# 180V_PSU.net
KiCad netlist of a schematic drawn in EAGLE
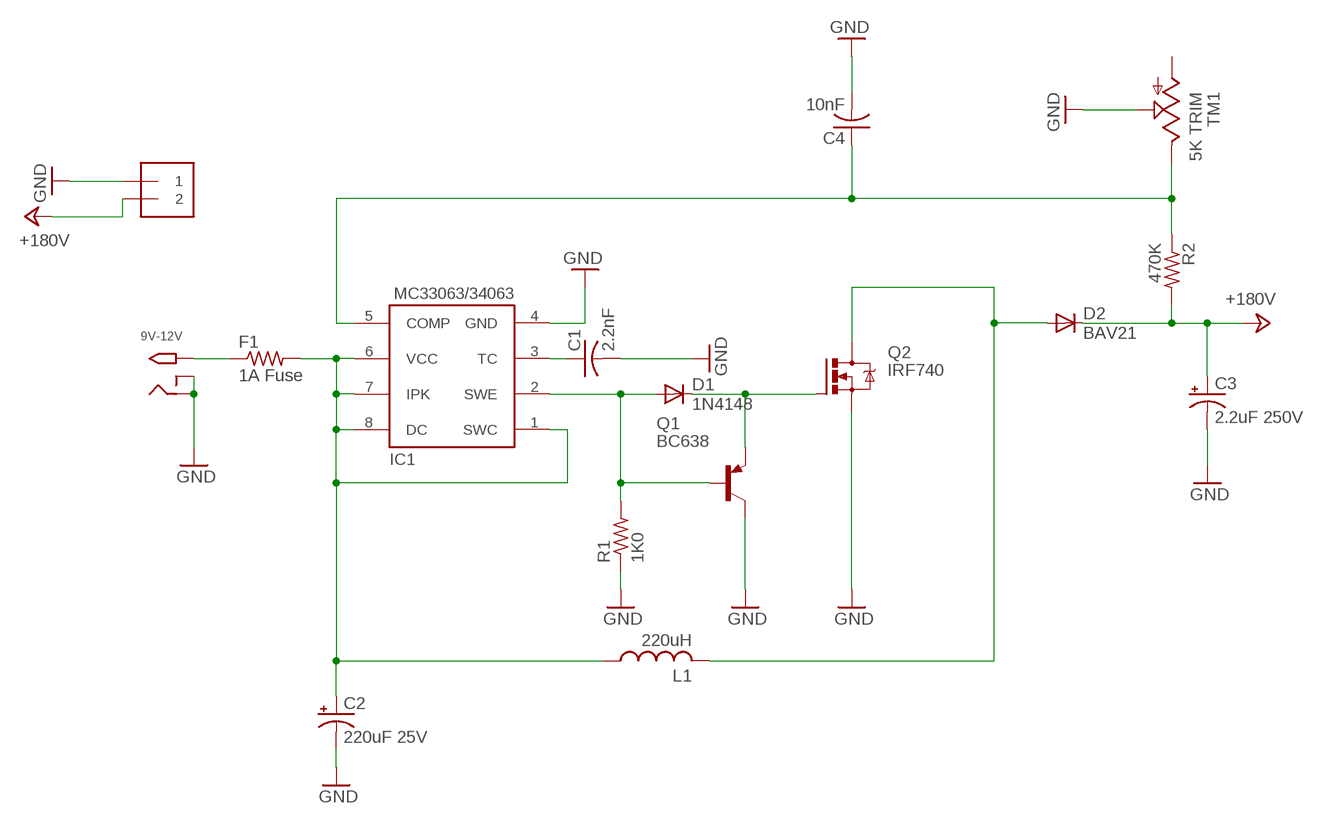
[diagram p0: schematic, sheet 1]

(export (version "E")
  (design (tool "Eeschema 10.0.6"))
  (components
    (comp (ref "9V-12V")
      (value "2.1MMJACKTHM")
      (footprint "eagle-import:PJ-102A")
      (libsource (lib "eagle-import") (part "2.1MMJACKTHM"))
    )
    (comp (ref "C1")
      (value "2.2nF")
      (footprint "eagle-import:C025-030X050")
      (libsource (lib "eagle-import") (part "C-US025-030X050"))
    )
    (comp (ref "C2")
      (value "220uF 25V")
      (footprint "eagle-import:E2,5-6")
      (libsource (lib "eagle-import") (part "CPOL-USE2.5-6"))
    )
    (comp (ref "C3")
      (value "2.2uF 250V")
      (footprint "eagle-import:E2,5-6")
      (libsource (lib "eagle-import") (part "CPOL-USE2.5-6"))
    )
    (comp (ref "C4")
      (value "10nF")
      (footprint "eagle-import:C025-030X050")
      (libsource (lib "eagle-import") (part "C-US025-030X050"))
    )
    (comp (ref "D1")
      (value "1N4148")
      (footprint "eagle-import:DO35-10")
      (libsource (lib "eagle-import") (part "1N4148DO35-10"))
    )
    (comp (ref "D2")
      (value "BAV21")
      (footprint "eagle-import:DO35-10")
      (libsource (lib "eagle-import") (part "BAV21"))
    )
    (comp (ref "F1")
      (value "1A Fuse")
      (footprint "eagle-import:0204_5")
      (libsource (lib "eagle-import") (part "R-US_0204/5"))
    )
    (comp (ref "IC1")
      (value "MC33063/MC34063P")
      (footprint "eagle-import:DIL08")
      (libsource (lib "eagle-import") (part "MC33063/MC34063P"))
    )
    (comp (ref "J1")
      (value "1X2-3.5MM")
      (footprint "eagle-import:1X2-3.5MM")
      (libsource (lib "eagle-import") (part "1X2-3.5MM"))
    )
    (comp (ref "L1")
      (value "220uH")
      (footprint "eagle-import:6000-XXXX-RC")
      (libsource (lib "eagle-import") (part "L-US6000-XXX-RC"))
    )
    (comp (ref "Q1")
      (value "BC638")
      (footprint "eagle-import:TO92-BCE")
      (libsource (lib "eagle-import") (part "BC638"))
    )
    (comp (ref "Q2")
      (value "IRF740")
      (footprint "eagle-import:TO220BV")
      (libsource (lib "eagle-import") (part "IRF740"))
    )
    (comp (ref "R1")
      (value "1K0")
      (footprint "eagle-import:0207_10")
      (libsource (lib "eagle-import") (part "resistor_R-US_0207/10"))
    )
    (comp (ref "R2")
      (value "470K")
      (footprint "eagle-import:0207_10")
      (libsource (lib "eagle-import") (part "resistor_R-US_0207/10"))
    )
    (comp (ref "TM1")
      (value "5K TRIM")
      (footprint "eagle-import:6MM")
      (libsource (lib "eagle-import") (part "TRIM"))
    )
  )
  (nets
    (net (code "1") (name "+180V") (class "Default")
      (node (ref "C3") (pin "+") (pinfunction "+_+") (pintype "passive"))
      (node (ref "D2") (pin "C") (pinfunction "C_C") (pintype "passive"))
      (node (ref "J1") (pin "2") (pinfunction "2_2") (pintype "passive"))
      (node (ref "R2") (pin "2") (pinfunction "2_2") (pintype "passive"))
    )
    (net (code "2") (name "GND") (class "Default")
      (node (ref "9V-12V") (pin "RING") (pinfunction "RING_RING") (pintype "bidirectional"))
      (node (ref "9V-12V") (pin "RING_SW") (pinfunction "RING_SW_RING_SW") (pintype "bidirectional"))
      (node (ref "C1") (pin "2") (pinfunction "2_2") (pintype "passive"))
      (node (ref "C2") (pin "-") (pinfunction "-_-") (pintype "passive"))
      (node (ref "C3") (pin "-") (pinfunction "-_-") (pintype "passive"))
      (node (ref "C4") (pin "2") (pinfunction "2_2") (pintype "passive"))
      (node (ref "IC1") (pin "4") (pinfunction "GND_4") (pintype "power_in"))
      (node (ref "J1") (pin "1") (pinfunction "1_1") (pintype "passive"))
      (node (ref "Q1") (pin "C") (pinfunction "C_C") (pintype "passive"))
      (node (ref "Q2") (pin "S") (pinfunction "S_S") (pintype "passive"))
      (node (ref "R1") (pin "1") (pinfunction "1_1") (pintype "passive"))
      (node (ref "TM1") (pin "S") (pinfunction "S_S") (pintype "passive"))
    )
    (net (code "3") (name "Net-(9V-12V-PadTIP)") (class "Default")
      (node (ref "9V-12V") (pin "TIP") (pinfunction "TIP_TIP") (pintype "bidirectional"))
      (node (ref "F1") (pin "1") (pinfunction "1_1") (pintype "passive"))
    )
    (net (code "4") (name "Net-(D1-PadC)") (class "Default")
      (node (ref "D1") (pin "C") (pinfunction "C_C") (pintype "passive"))
      (node (ref "Q1") (pin "E") (pinfunction "E_E") (pintype "passive"))
      (node (ref "Q2") (pin "G") (pinfunction "G_G") (pintype "passive"))
    )
    (net (code "5") (name "Net-(D2-PadA)") (class "Default")
      (node (ref "D2") (pin "A") (pinfunction "A_A") (pintype "passive"))
      (node (ref "L1") (pin "2") (pinfunction "2_2") (pintype "passive"))
      (node (ref "Q2") (pin "D") (pinfunction "D_D") (pintype "passive"))
    )
    (net (code "6") (name "Net-(IC1-COMP)") (class "Default")
      (node (ref "C4") (pin "1") (pinfunction "1_1") (pintype "passive"))
      (node (ref "IC1") (pin "5") (pinfunction "COMP_5") (pintype "input"))
      (node (ref "R2") (pin "1") (pinfunction "1_1") (pintype "passive"))
      (node (ref "TM1") (pin "E") (pinfunction "E_E") (pintype "passive"))
    )
    (net (code "7") (name "Net-(IC1-DC)") (class "Default")
      (node (ref "C2") (pin "+") (pinfunction "+_+") (pintype "passive"))
      (node (ref "F1") (pin "2") (pinfunction "2_2") (pintype "passive"))
      (node (ref "IC1") (pin "1") (pinfunction "SWC_1") (pintype "input"))
      (node (ref "IC1") (pin "6") (pinfunction "VCC_6") (pintype "power_in"))
      (node (ref "IC1") (pin "7") (pinfunction "IPK_7") (pintype "bidirectional"))
      (node (ref "IC1") (pin "8") (pinfunction "DC_8") (pintype "input"))
      (node (ref "L1") (pin "1") (pinfunction "1_1") (pintype "passive"))
    )
    (net (code "8") (name "Net-(IC1-SWE)") (class "Default")
      (node (ref "D1") (pin "A") (pinfunction "A_A") (pintype "passive"))
      (node (ref "IC1") (pin "2") (pinfunction "SWE_2") (pintype "input"))
      (node (ref "Q1") (pin "B") (pinfunction "B_B") (pintype "passive"))
      (node (ref "R1") (pin "2") (pinfunction "2_2") (pintype "passive"))
    )
    (net (code "9") (name "Net-(IC1-TC)") (class "Default")
      (node (ref "C1") (pin "1") (pinfunction "1_1") (pintype "passive"))
      (node (ref "IC1") (pin "3") (pinfunction "TC_3") (pintype "input"))
    )
    (net (code "10") (name "unconnected-(TM1-PadA)") (class "Default")
      (node (ref "TM1") (pin "A") (pinfunction "A_A") (pintype "passive"))
    )
  )
)
